# DXP.net
KiCad netlist of a schematic drawn in Altium Designer
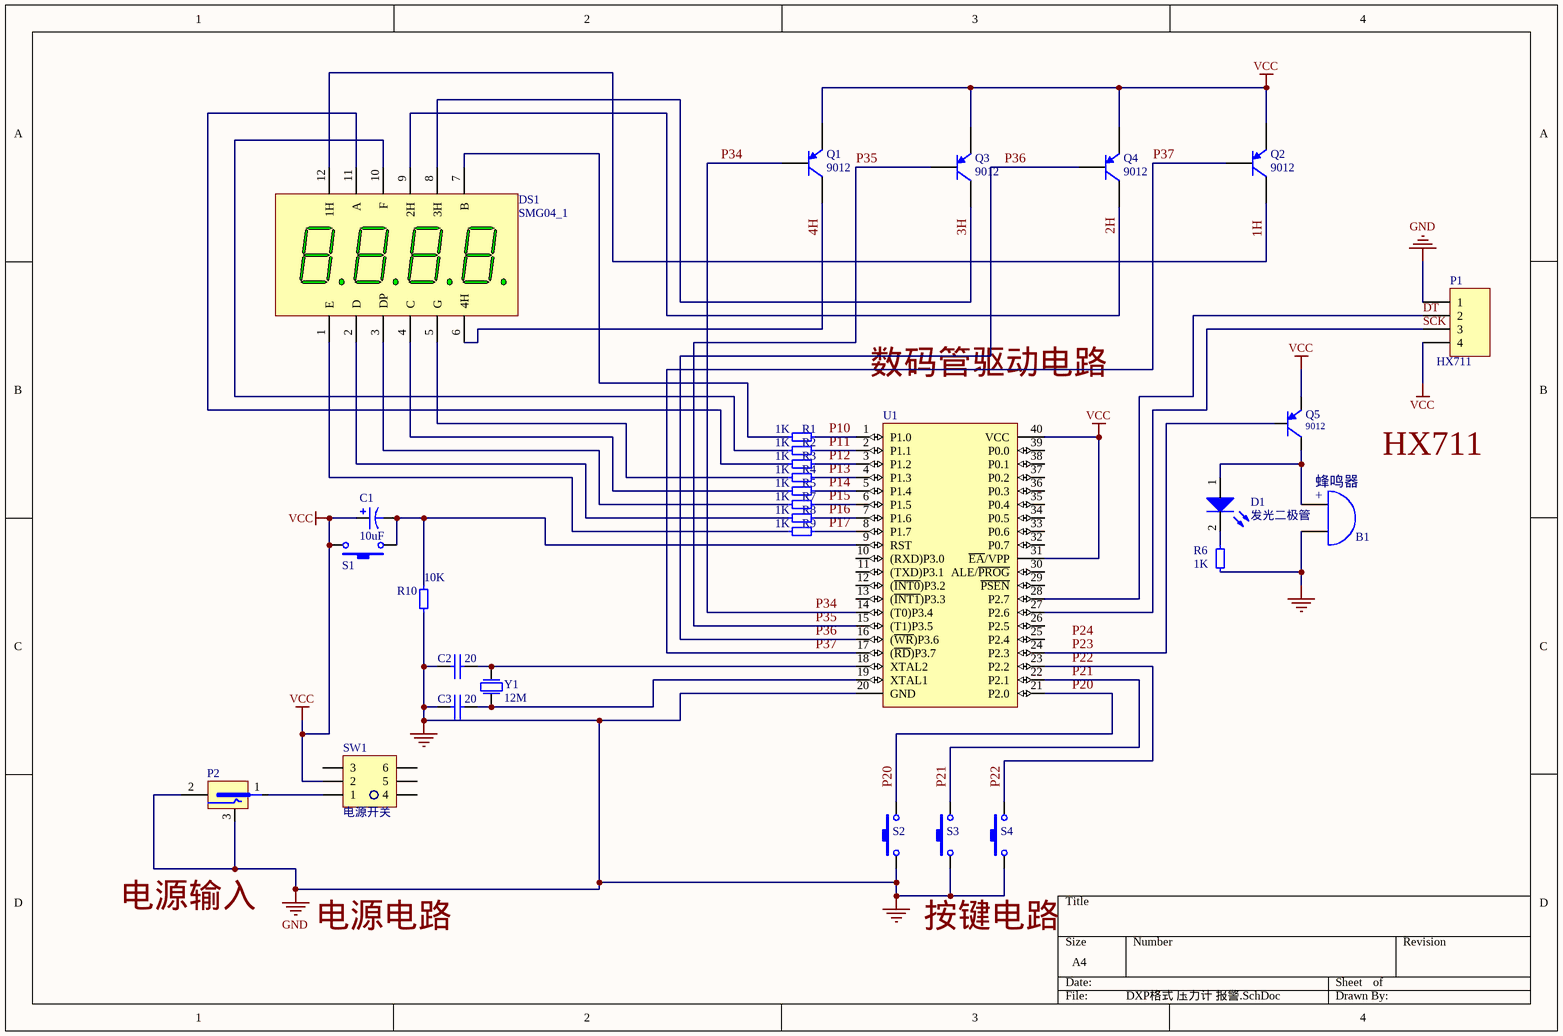
[diagram p0: DXP格式 压力计 报警.SchDoc]

(export (version "E")
  (design (tool "Eeschema 10.0.6"))
  (components
    (comp (ref "B1")
      (value "蜂鸣器")
      (footprint "Bett")
      (description "Bell")
      (libsource (lib "*") (part "BELL"))
    )
    (comp (ref "C1")
      (value "10uF")
      (footprint "C_10")
      (description "Polarized Capacitor (Radial)")
      (fields (field (name "PUBLISHER") "Altium Limited"))
      (libsource (lib "*") (part "Cap Pol1"))
    )
    (comp (ref "C2") (value "20") (footprint "CAP CP") (description "电容") (libsource (lib "*") (part "CAP")))
    (comp (ref "C3") (value "20") (footprint "CAP CP") (description "电容") (libsource (lib "*") (part "CAP")))
    (comp (ref "D1") (value "发光二极管") (footprint "LED直插") (libsource (lib "*") (part "D")))
    (comp (ref "DS1") (value "SMG04_1") (footprint "SMG04") (libsource (lib "*") (part "SMG04_1")))
    (comp (ref "P1")
      (value "HX711")
      (footprint "HX711")
      (description "Header, 4-Pin")
      (fields (field (name "PUBLISHER") "Altium Limited"))
      (libsource (lib "Miscellaneous Connectors") (part "Header 4"))
    )
    (comp (ref "P2") (value "电源输入") (footprint "DC2.1") (libsource (lib "我自己的") (part "POWER")))
    (comp (ref "Q1")
      (value "9012")
      (footprint "s三极管直插")
      (description "PNP General Purpose Amplifier")
      (fields (field (name "PUBLISHER") "Altium Limited"))
      (libsource (lib "*") (part "2N3906"))
    )
    (comp (ref "Q2")
      (value "9012")
      (footprint "s三极管直插")
      (description "PNP General Purpose Amplifier")
      (fields (field (name "PUBLISHER") "Altium Limited"))
      (libsource (lib "*") (part "2N3906"))
    )
    (comp (ref "Q3")
      (value "9012")
      (footprint "s三极管直插")
      (description "PNP General Purpose Amplifier")
      (fields (field (name "PUBLISHER") "Altium Limited"))
      (libsource (lib "*") (part "2N3906"))
    )
    (comp (ref "Q4")
      (value "9012")
      (footprint "s三极管直插")
      (description "PNP General Purpose Amplifier")
      (fields (field (name "PUBLISHER") "Altium Limited"))
      (libsource (lib "*") (part "2N3906"))
    )
    (comp (ref "Q5")
      (value "9012")
      (footprint "s三极管直插")
      (description "PNP General Purpose Amplifier")
      (fields (field (name "PUBLISHER") "Altium Limited"))
      (libsource (lib "") (part "2N3906_1"))
    )
    (comp (ref "R1") (value "1K") (footprint "AXIAL0.3") (libsource (lib "*") (part "RES2")))
    (comp (ref "R2") (value "1K") (footprint "AXIAL0.3") (libsource (lib "*") (part "RES2")))
    (comp (ref "R3") (value "1K") (footprint "AXIAL0.3") (libsource (lib "*") (part "RES2")))
    (comp (ref "R4") (value "1K") (footprint "AXIAL0.3") (libsource (lib "*") (part "RES2")))
    (comp (ref "R5") (value "1K") (footprint "AXIAL0.3") (libsource (lib "*") (part "RES2")))
    (comp (ref "R6") (value "1K") (footprint "AXIAL0.3") (libsource (lib "*") (part "RES2")))
    (comp (ref "R7") (value "1K") (footprint "AXIAL0.3") (libsource (lib "*") (part "RES2")))
    (comp (ref "R8") (value "1K") (footprint "AXIAL0.3") (libsource (lib "*") (part "RES2")))
    (comp (ref "R9") (value "1K") (footprint "AXIAL0.3") (libsource (lib "*") (part "RES2")))
    (comp (ref "R10") (value "10K") (footprint "AXIAL0.3") (libsource (lib "*") (part "RES2")))
    (comp (ref "S1")
      (value "SW-PB")
      (footprint "key")
      (description "Switch")
      (fields (field (name "PUBLISHER") "Altium Limited"))
      (libsource (lib "*") (part "SW-PB"))
    )
    (comp (ref "S2")
      (value "SW-PB")
      (footprint "key")
      (description "Switch")
      (fields (field (name "PUBLISHER") "Altium Limited"))
      (libsource (lib "*") (part "SW-PB"))
    )
    (comp (ref "S3")
      (value "SW-PB")
      (footprint "key")
      (description "Switch")
      (fields (field (name "PUBLISHER") "Altium Limited"))
      (libsource (lib "*") (part "SW-PB"))
    )
    (comp (ref "S4")
      (value "SW-PB")
      (footprint "key")
      (description "Switch")
      (fields (field (name "PUBLISHER") "Altium Limited"))
      (libsource (lib "*") (part "SW-PB"))
    )
    (comp (ref "SW1") (value "电源开关") (footprint "sw_自锁 1") (libsource (lib "我自己的") (part "SW1")))
    (comp (ref "U1") (value "STC89C52") (footprint "DIP40 - 做板") (libsource (lib "*") (part "U1")))
    (comp (ref "Y1")
      (value "12M")
      (footprint "XTAL")
      (description "Crystal Oscillator")
      (libsource (lib "*") (part "16M"))
    )
  )
  (nets
    (net (code "1") (name "/1H") (class "Default")
      (node (ref "DS1") (pin "12") (pinfunction "1H_12") (pintype "passive"))
      (node (ref "Q2") (pin "3") (pinfunction "C_3") (pintype "passive"))
    )
    (net (code "2") (name "/2H") (class "Default")
      (node (ref "DS1") (pin "9") (pinfunction "2H_9") (pintype "passive"))
      (node (ref "Q4") (pin "3") (pinfunction "C_3") (pintype "passive"))
    )
    (net (code "3") (name "/3H") (class "Default")
      (node (ref "DS1") (pin "8") (pinfunction "3H_8") (pintype "passive"))
      (node (ref "Q3") (pin "3") (pinfunction "C_3") (pintype "passive"))
    )
    (net (code "4") (name "/4H") (class "Default")
      (node (ref "DS1") (pin "6") (pinfunction "4H_6") (pintype "passive"))
      (node (ref "Q1") (pin "3") (pinfunction "C_3") (pintype "passive"))
    )
    (net (code "5") (name "/DT") (class "Default")
      (node (ref "P1") (pin "2") (pinfunction "2_2") (pintype "passive"))
      (node (ref "U1") (pin "28") (pinfunction "P2.7_28") (pintype "bidirectional"))
    )
    (net (code "7") (name "/P10") (class "Default")
      (node (ref "R1") (pin "2") (pinfunction "2_2") (pintype "passive"))
      (node (ref "U1") (pin "1") (pinfunction "P1.0_1") (pintype "bidirectional"))
    )
    (net (code "8") (name "/P11") (class "Default")
      (node (ref "R2") (pin "2") (pinfunction "2_2") (pintype "passive"))
      (node (ref "U1") (pin "2") (pinfunction "P1.1_2") (pintype "bidirectional"))
    )
    (net (code "9") (name "/P12") (class "Default")
      (node (ref "R3") (pin "2") (pinfunction "2_2") (pintype "passive"))
      (node (ref "U1") (pin "3") (pinfunction "P1.2_3") (pintype "bidirectional"))
    )
    (net (code "10") (name "/P13") (class "Default")
      (node (ref "R4") (pin "2") (pinfunction "2_2") (pintype "passive"))
      (node (ref "U1") (pin "4") (pinfunction "P1.3_4") (pintype "bidirectional"))
    )
    (net (code "11") (name "/P14") (class "Default")
      (node (ref "R5") (pin "2") (pinfunction "2_2") (pintype "passive"))
      (node (ref "U1") (pin "5") (pinfunction "P1.4_5") (pintype "bidirectional"))
    )
    (net (code "12") (name "/P15") (class "Default")
      (node (ref "R7") (pin "2") (pinfunction "2_2") (pintype "passive"))
      (node (ref "U1") (pin "6") (pinfunction "P1.5_6") (pintype "bidirectional"))
    )
    (net (code "13") (name "/P16") (class "Default")
      (node (ref "R8") (pin "2") (pinfunction "2_2") (pintype "passive"))
      (node (ref "U1") (pin "7") (pinfunction "P1.6_7") (pintype "bidirectional"))
    )
    (net (code "14") (name "/P17") (class "Default")
      (node (ref "R9") (pin "2") (pinfunction "2_2") (pintype "passive"))
      (node (ref "U1") (pin "8") (pinfunction "P1.7_8") (pintype "bidirectional"))
    )
    (net (code "15") (name "/P20") (class "Default")
      (node (ref "S2") (pin "2") (pinfunction "2_2") (pintype "passive"))
      (node (ref "U1") (pin "21") (pinfunction "P2.0_21") (pintype "bidirectional"))
    )
    (net (code "16") (name "/P21") (class "Default")
      (node (ref "S3") (pin "2") (pinfunction "2_2") (pintype "passive"))
      (node (ref "U1") (pin "22") (pinfunction "P2.1_22") (pintype "bidirectional"))
    )
    (net (code "17") (name "/P22") (class "Default")
      (node (ref "S4") (pin "2") (pinfunction "2_2") (pintype "passive"))
      (node (ref "U1") (pin "23") (pinfunction "P2.2_23") (pintype "bidirectional"))
    )
    (net (code "18") (name "/P23") (class "Default")
      (node (ref "Q5") (pin "2") (pinfunction "B_2") (pintype "passive"))
      (node (ref "U1") (pin "24") (pinfunction "P2.3_24") (pintype "bidirectional"))
    )
    (net (code "20") (name "/P34") (class "Default")
      (node (ref "Q1") (pin "2") (pinfunction "B_2") (pintype "passive"))
      (node (ref "U1") (pin "14") (pinfunction "(T0)P3.4_14") (pintype "bidirectional"))
    )
    (net (code "21") (name "/P35") (class "Default")
      (node (ref "Q3") (pin "2") (pinfunction "B_2") (pintype "passive"))
      (node (ref "U1") (pin "15") (pinfunction "(T1)P3.5_15") (pintype "bidirectional"))
    )
    (net (code "22") (name "/P36") (class "Default")
      (node (ref "Q4") (pin "2") (pinfunction "B_2") (pintype "passive"))
      (node (ref "U1") (pin "16") (pinfunction "(~{WR})P3.6_16") (pintype "bidirectional"))
    )
    (net (code "23") (name "/P37") (class "Default")
      (node (ref "Q2") (pin "2") (pinfunction "B_2") (pintype "passive"))
      (node (ref "U1") (pin "17") (pinfunction "(~{RD})P3.7_17") (pintype "bidirectional"))
    )
    (net (code "24") (name "/SCK") (class "Default")
      (node (ref "P1") (pin "3") (pinfunction "3_3") (pintype "passive"))
      (node (ref "U1") (pin "27") (pinfunction "P2.6_27") (pintype "bidirectional"))
    )
    (net (code "29") (name "GND") (class "Default")
      (node (ref "B1") (pin "2") (pinfunction "B_2") (pintype "passive"))
      (node (ref "C2") (pin "1") (pinfunction "1_1") (pintype "passive"))
      (node (ref "C3") (pin "1") (pinfunction "1_1") (pintype "passive"))
      (node (ref "P1") (pin "1") (pinfunction "1_1") (pintype "passive"))
      (node (ref "P2") (pin "2") (pintype "passive"))
      (node (ref "P2") (pin "3") (pintype "passive"))
      (node (ref "R10") (pin "1") (pinfunction "1_1") (pintype "passive"))
      (node (ref "R6") (pin "2") (pinfunction "2_2") (pintype "passive"))
      (node (ref "S2") (pin "1") (pinfunction "1_1") (pintype "passive"))
      (node (ref "S3") (pin "1") (pinfunction "1_1") (pintype "passive"))
      (node (ref "S4") (pin "1") (pinfunction "1_1") (pintype "passive"))
      (node (ref "U1") (pin "20") (pinfunction "GND_20") (pintype "power_in"))
    )
    (net (code "30") (name "Net-(B1-A)") (class "Default")
      (node (ref "B1") (pin "1") (pinfunction "A_1") (pintype "passive"))
      (node (ref "D1") (pin "1") (pintype "passive"))
      (node (ref "Q5") (pin "3") (pinfunction "C_3") (pintype "passive"))
    )
    (net (code "31") (name "Net-(D1-Pad2)") (class "Default")
      (node (ref "D1") (pin "2") (pintype "passive"))
      (node (ref "R6") (pin "1") (pinfunction "1_1") (pintype "passive"))
    )
    (net (code "32") (name "Net-(DS1-A)") (class "Default")
      (node (ref "DS1") (pin "11") (pinfunction "A_11") (pintype "passive"))
      (node (ref "R3") (pin "1") (pinfunction "1_1") (pintype "passive"))
    )
    (net (code "33") (name "Net-(DS1-B)") (class "Default")
      (node (ref "DS1") (pin "7") (pinfunction "B_7") (pintype "passive"))
      (node (ref "R1") (pin "1") (pinfunction "1_1") (pintype "passive"))
    )
    (net (code "34") (name "Net-(DS1-C)") (class "Default")
      (node (ref "DS1") (pin "4") (pinfunction "C_4") (pintype "passive"))
      (node (ref "R5") (pin "1") (pinfunction "1_1") (pintype "passive"))
    )
    (net (code "35") (name "Net-(DS1-D)") (class "Default")
      (node (ref "DS1") (pin "2") (pinfunction "D_2") (pintype "passive"))
      (node (ref "R8") (pin "1") (pinfunction "1_1") (pintype "passive"))
    )
    (net (code "36") (name "Net-(DS1-DP)") (class "Default")
      (node (ref "DS1") (pin "3") (pinfunction "DP_3") (pintype "passive"))
      (node (ref "R7") (pin "1") (pinfunction "1_1") (pintype "passive"))
    )
    (net (code "37") (name "Net-(DS1-E)") (class "Default")
      (node (ref "DS1") (pin "1") (pinfunction "E_1") (pintype "passive"))
      (node (ref "R9") (pin "1") (pinfunction "1_1") (pintype "passive"))
    )
    (net (code "38") (name "Net-(DS1-F)") (class "Default")
      (node (ref "DS1") (pin "10") (pinfunction "F_10") (pintype "passive"))
      (node (ref "R2") (pin "1") (pinfunction "1_1") (pintype "passive"))
    )
    (net (code "39") (name "Net-(DS1-G)") (class "Default")
      (node (ref "DS1") (pin "5") (pinfunction "G_5") (pintype "passive"))
      (node (ref "R4") (pin "1") (pinfunction "1_1") (pintype "passive"))
    )
    (net (code "40") (name "Net-(P2-Pad1)") (class "Default")
      (node (ref "P2") (pin "1") (pintype "passive"))
      (node (ref "SW1") (pin "1") (pinfunction "1_1") (pintype "passive"))
    )
    (net (code "41") (name "Net-(U1-RST)") (class "Default")
      (node (ref "C1") (pin "2") (pinfunction "2_2") (pintype "passive"))
      (node (ref "R10") (pin "2") (pinfunction "2_2") (pintype "passive"))
      (node (ref "S1") (pin "1") (pinfunction "1_1") (pintype "passive"))
      (node (ref "U1") (pin "9") (pinfunction "RST_9") (pintype "bidirectional"))
    )
    (net (code "42") (name "Net-(U1-XTAL1)") (class "Default")
      (node (ref "C3") (pin "2") (pinfunction "2_2") (pintype "passive"))
      (node (ref "U1") (pin "19") (pinfunction "XTAL1_19") (pintype "bidirectional"))
      (node (ref "Y1") (pin "2") (pinfunction "P2_2") (pintype "passive"))
    )
    (net (code "43") (name "Net-(U1-XTAL2)") (class "Default")
      (node (ref "C2") (pin "2") (pinfunction "2_2") (pintype "passive"))
      (node (ref "U1") (pin "18") (pinfunction "XTAL2_18") (pintype "bidirectional"))
      (node (ref "Y1") (pin "1") (pinfunction "P1_1") (pintype "passive"))
    )
    (net (code "44") (name "VCC") (class "Default")
      (node (ref "C1") (pin "1") (pinfunction "1_1") (pintype "passive"))
      (node (ref "P1") (pin "4") (pinfunction "4_4") (pintype "passive"))
      (node (ref "Q1") (pin "1") (pinfunction "E_1") (pintype "passive"))
      (node (ref "Q2") (pin "1") (pinfunction "E_1") (pintype "passive"))
      (node (ref "Q3") (pin "1") (pinfunction "E_1") (pintype "passive"))
      (node (ref "Q4") (pin "1") (pinfunction "E_1") (pintype "passive"))
      (node (ref "Q5") (pin "1") (pinfunction "E_1") (pintype "passive"))
      (node (ref "S1") (pin "2") (pinfunction "2_2") (pintype "passive"))
      (node (ref "SW1") (pin "2") (pinfunction "2_2") (pintype "passive"))
      (node (ref "U1") (pin "31") (pinfunction "~{EA}/VPP_31") (pintype "power_in"))
      (node (ref "U1") (pin "40") (pinfunction "VCC_40") (pintype "power_in"))
    )
    (net (code "45") (name "unconnected-(SW1-Pad3)") (class "Default")
      (node (ref "SW1") (pin "3") (pinfunction "3_3") (pintype "passive"))
    )
    (net (code "46") (name "unconnected-(SW1-Pad4)") (class "Default")
      (node (ref "SW1") (pin "4") (pinfunction "4_4") (pintype "passive"))
    )
    (net (code "47") (name "unconnected-(SW1-Pad5)") (class "Default")
      (node (ref "SW1") (pin "5") (pinfunction "5_5") (pintype "passive"))
    )
    (net (code "48") (name "unconnected-(SW1-Pad6)") (class "Default")
      (node (ref "SW1") (pin "6") (pinfunction "6_6") (pintype "passive"))
    )
    (net (code "49") (name "unconnected-(U1-(RXD)P3.0-Pad10)") (class "Default")
      (node (ref "U1") (pin "10") (pinfunction "(RXD)P3.0_10") (pintype "bidirectional"))
    )
    (net (code "50") (name "unconnected-(U1-(TXD)P3.1-Pad11)") (class "Default")
      (node (ref "U1") (pin "11") (pinfunction "(TXD)P3.1_11") (pintype "bidirectional"))
    )
    (net (code "51") (name "unconnected-(U1-(~{INT0})P3.2-Pad12)") (class "Default")
      (node (ref "U1") (pin "12") (pinfunction "(~{INT0})P3.2_12") (pintype "bidirectional"))
    )
    (net (code "52") (name "unconnected-(U1-(~{INT1})P3.3-Pad13)") (class "Default")
      (node (ref "U1") (pin "13") (pinfunction "(~{INT1})P3.3_13") (pintype "bidirectional"))
    )
    (net (code "53") (name "unconnected-(U1-ALE{slash}~{PROG}-Pad30)") (class "Default")
      (node (ref "U1") (pin "30") (pinfunction "ALE/~{PROG}_30") (pintype "bidirectional"))
    )
    (net (code "54") (name "unconnected-(U1-P0.0-Pad39)") (class "Default")
      (node (ref "U1") (pin "39") (pinfunction "P0.0_39") (pintype "bidirectional"))
    )
    (net (code "55") (name "unconnected-(U1-P0.1-Pad38)") (class "Default")
      (node (ref "U1") (pin "38") (pinfunction "P0.1_38") (pintype "bidirectional"))
    )
    (net (code "56") (name "unconnected-(U1-P0.2-Pad37)") (class "Default")
      (node (ref "U1") (pin "37") (pinfunction "P0.2_37") (pintype "bidirectional"))
    )
    (net (code "57") (name "unconnected-(U1-P0.3-Pad36)") (class "Default")
      (node (ref "U1") (pin "36") (pinfunction "P0.3_36") (pintype "bidirectional"))
    )
    (net (code "58") (name "unconnected-(U1-P0.4-Pad35)") (class "Default")
      (node (ref "U1") (pin "35") (pinfunction "P0.4_35") (pintype "bidirectional"))
    )
    (net (code "59") (name "unconnected-(U1-P0.5-Pad34)") (class "Default")
      (node (ref "U1") (pin "34") (pinfunction "P0.5_34") (pintype "bidirectional"))
    )
    (net (code "60") (name "unconnected-(U1-P0.6-Pad33)") (class "Default")
      (node (ref "U1") (pin "33") (pinfunction "P0.6_33") (pintype "bidirectional"))
    )
    (net (code "61") (name "unconnected-(U1-P0.7-Pad32)") (class "Default")
      (node (ref "U1") (pin "32") (pinfunction "P0.7_32") (pintype "bidirectional"))
    )
    (net (code "62") (name "unconnected-(U1-P2.4-Pad25)") (class "Default")
      (node (ref "U1") (pin "25") (pinfunction "P2.4_25") (pintype "bidirectional"))
    )
    (net (code "63") (name "unconnected-(U1-P2.5-Pad26)") (class "Default")
      (node (ref "U1") (pin "26") (pinfunction "P2.5_26") (pintype "bidirectional"))
    )
    (net (code "64") (name "unconnected-(U1-~{PSEN}-Pad29)") (class "Default")
      (node (ref "U1") (pin "29") (pinfunction "~{PSEN}_29") (pintype "bidirectional"))
    )
  )
)
